# hx_esp32c5_cam.net
KiCad netlist of a schematic drawn in EasyEDA Pro
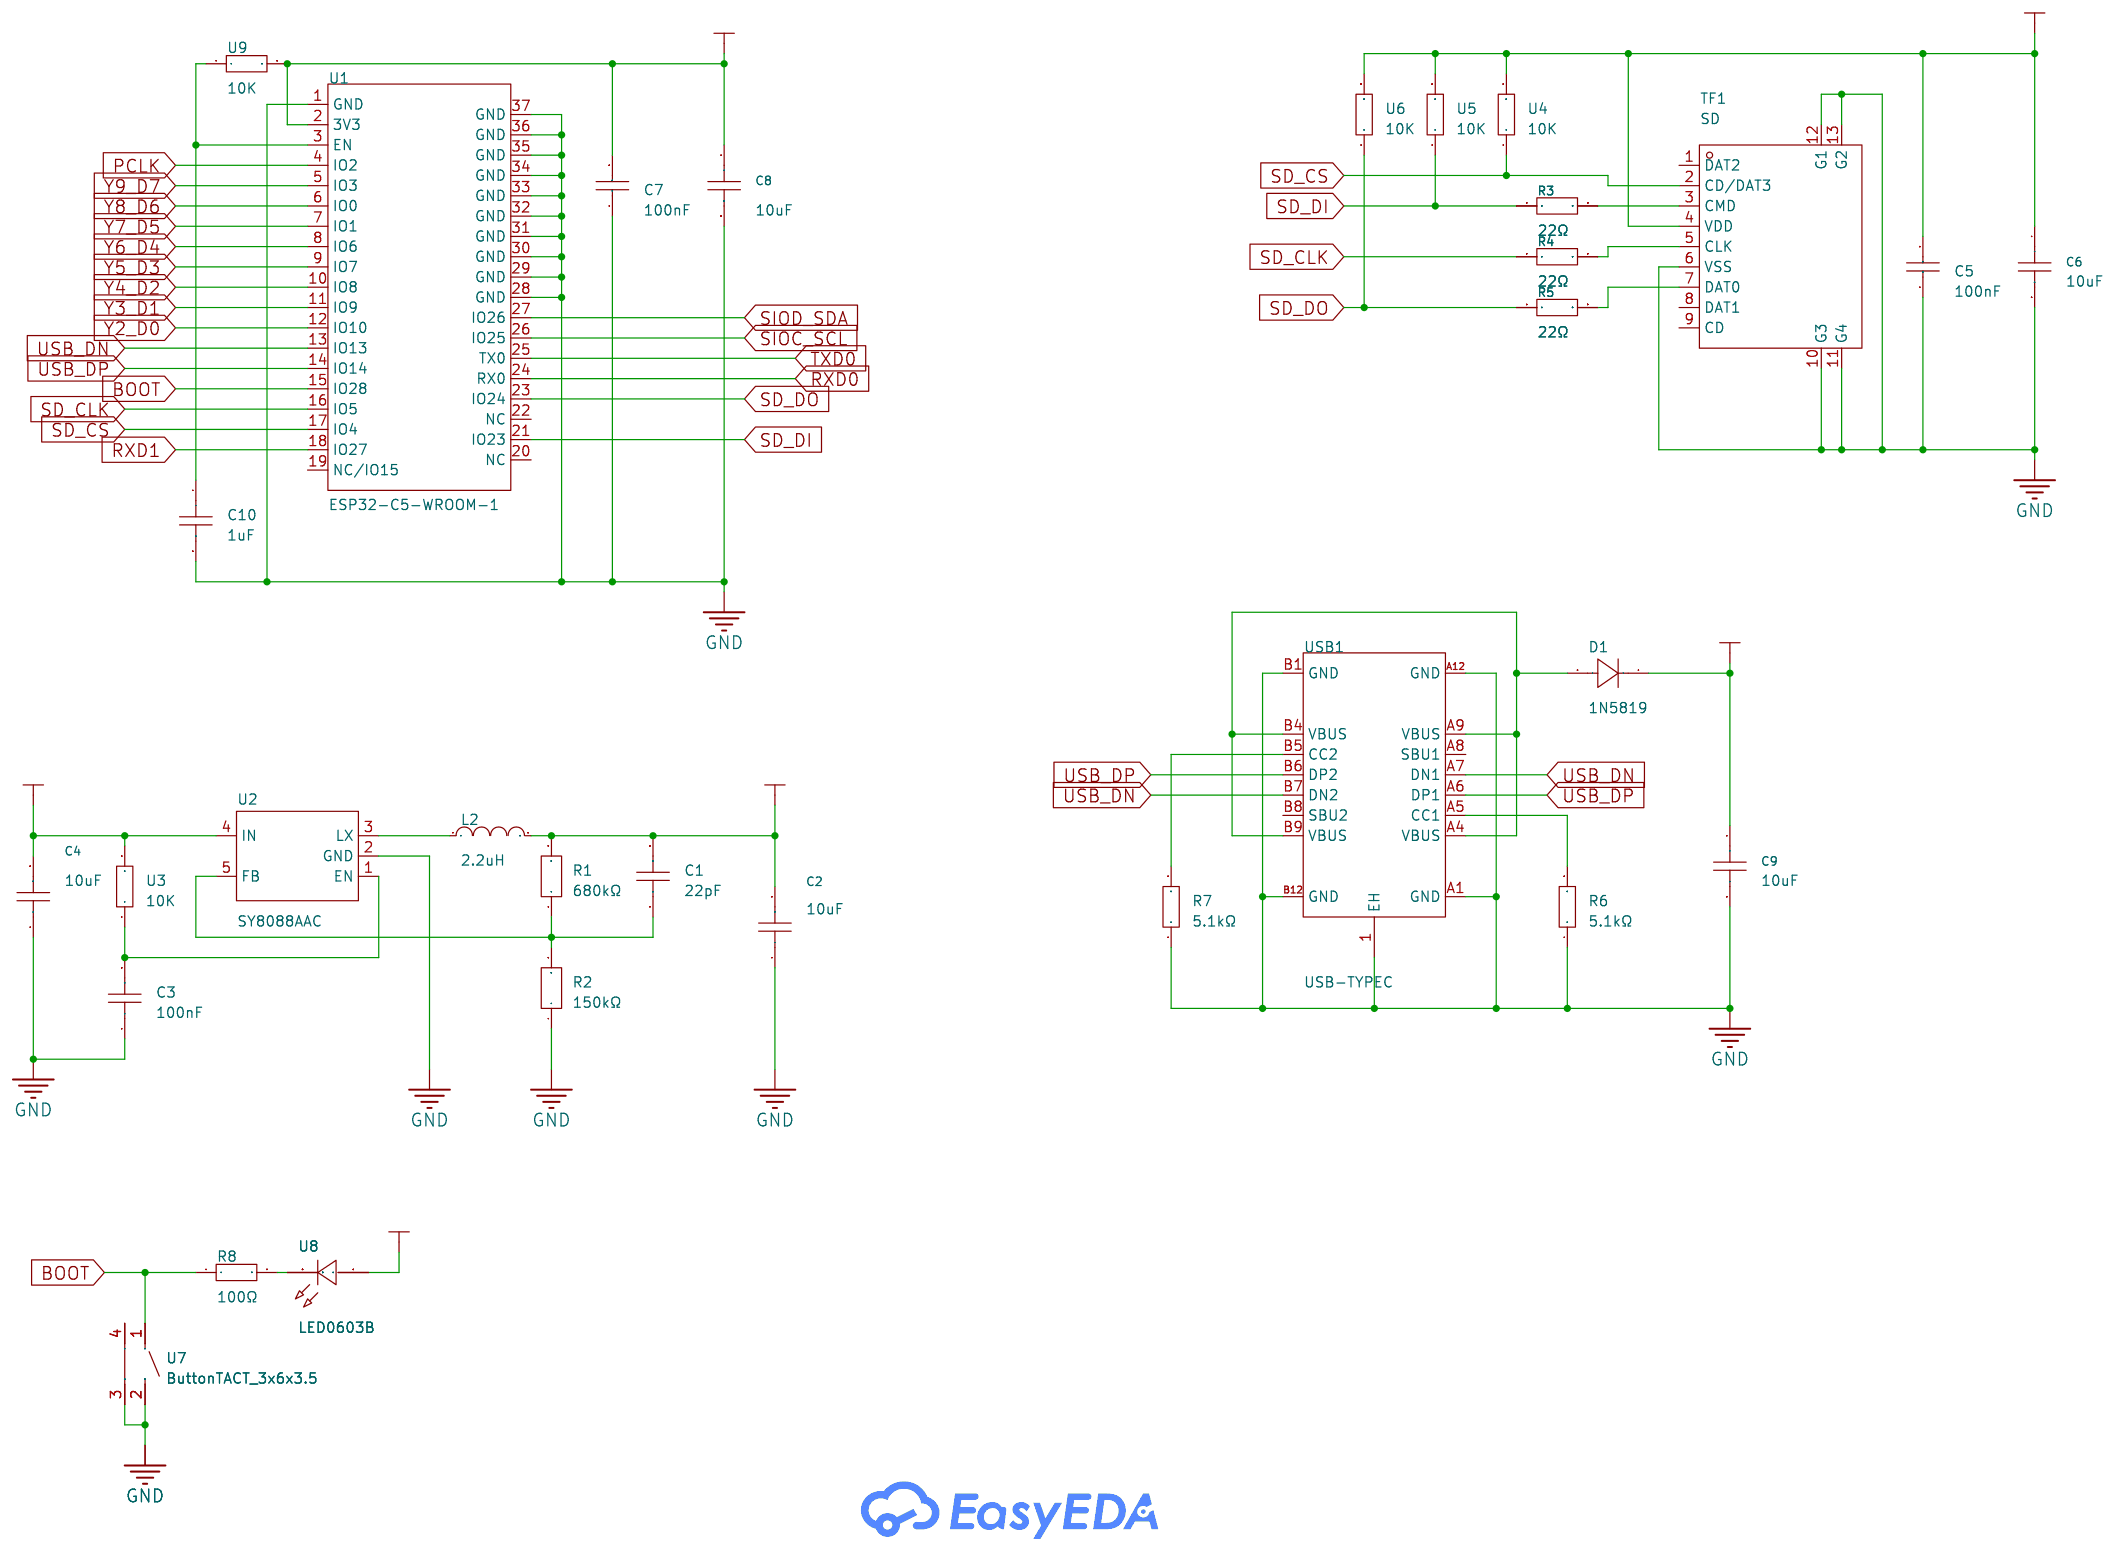
[diagram p0: schematic sheet]

(export (version "E")
  (design (tool "Eeschema 10.0.6"))
  (components
    (comp (ref "C1")
      (value "22pF")
      (footprint "easyedapro:C0603")
      (description "Capacitance:22pF Tolerance:±1% Tolerance:±1% Voltage Rating:50V Temperature Coefficient:NP0")
      (fields
        (field (name "Manufacturer Part") "CC0603FPNPO9BN220")
        (field (name "Manufacturer") "YAGEO(国巨)")
      )
      (libsource (lib "easyedapro") (part "CC0603FPNPO9BN220"))
    )
    (comp (ref "C2")
      (value "10uF")
      (footprint "easyedapro:C0603")
      (fields (field (name "Manufacturer") "SAMSUNG(三星)"))
      (libsource (lib "easyedapro") (part "10UF"))
    )
    (comp (ref "C3")
      (value "100nF")
      (footprint "easyedapro:C0805")
      (description "Capacitance:100nF Tolerance:±10% Tolerance:±10% Voltage Rating:50V Temperature Coefficient:X7R")
      (fields
        (field (name "Manufacturer Part") "CC0805KRX7R9BB104")
        (field (name "Manufacturer") "YAGEO(国巨)")
      )
      (libsource (lib "easyedapro") (part "CC0805KRX7R9BB104"))
    )
    (comp (ref "C4")
      (value "10uF")
      (footprint "easyedapro:C0603")
      (fields (field (name "Manufacturer") "SAMSUNG(三星)"))
      (libsource (lib "easyedapro") (part "10UF"))
    )
    (comp (ref "C5")
      (value "100nF")
      (footprint "easyedapro:C0805")
      (description "Capacitance:100nF Tolerance:±10% Tolerance:±10% Voltage Rating:100V Temperature Coefficient:X7R")
      (fields
        (field (name "Manufacturer Part") "CL21B104KCFNNNE")
        (field (name "Manufacturer") "SAMSUNG(三星)")
      )
      (libsource (lib "easyedapro") (part "CL21B104KCFNNNE"))
    )
    (comp (ref "C6")
      (value "10uF")
      (footprint "easyedapro:C0603")
      (fields (field (name "Manufacturer") "SAMSUNG(三星)"))
      (libsource (lib "easyedapro") (part "10UF"))
    )
    (comp (ref "C7")
      (value "100nF")
      (footprint "easyedapro:C0805")
      (description "Capacitance:100nF Tolerance:±10% Tolerance:±10% Voltage Rating:100V Temperature Coefficient:X7R")
      (fields
        (field (name "Manufacturer Part") "CL21B104KCFNNNE")
        (field (name "Manufacturer") "SAMSUNG(三星)")
      )
      (libsource (lib "easyedapro") (part "CL21B104KCFNNNE"))
    )
    (comp (ref "C8")
      (value "10uF")
      (footprint "easyedapro:C0603")
      (fields (field (name "Manufacturer") "SAMSUNG(三星)"))
      (libsource (lib "easyedapro") (part "10UF"))
    )
    (comp (ref "C9")
      (value "10uF")
      (footprint "easyedapro:C0603")
      (fields (field (name "Manufacturer") "SAMSUNG(三星)"))
      (libsource (lib "easyedapro") (part "10UF"))
    )
    (comp (ref "C10")
      (value "1uF")
      (footprint "easyedapro:C0603")
      (fields (field (name "Manufacturer Part") "CGB3B1X6S1C105K055AC") (field (name "Manufacturer") "TDK"))
      (libsource (lib "easyedapro") (part "CGB3B1X6S1C105K055AC"))
    )
    (comp (ref "D1")
      (value "1N5819")
      (footprint "easyedapro:SMA_L4.3-W2.7-LS5.1-RD")
      (libsource (lib "easyedapro") (part "1N5819_C2892330"))
    )
    (comp (ref "L2")
      (value "2.2uH")
      (footprint "easyedapro:IND-SMD_L2.0-W1.6_MHP201610")
      (description "Inductance:2.2uH Tolerance:±20% Tolerance:±20% Current Rating:1.6A DC Resistance(DCR):120mΩ")
      (fields
        (field (name "Manufacturer Part") "HPI201612P-2R2M")
        (field (name "Manufacturer") "3L COILS(三礼)")
      )
      (libsource (lib "easyedapro") (part "HPI201612P-2R2M"))
    )
    (comp (ref "R1")
      (value "680kΩ")
      (footprint "easyedapro:R0805")
      (fields
        (field (name "Manufacturer Part") "TC0525B6803T5E")
        (field (name "Manufacturer") "UNI-ROYAL(厚声)")
      )
      (libsource (lib "easyedapro") (part "TC0525B6803T5E"))
    )
    (comp (ref "R2")
      (value "150kΩ")
      (footprint "easyedapro:R0805")
      (fields
        (field (name "Manufacturer Part") "AS05W2J0154T5E")
        (field (name "Manufacturer") "UNI-ROYAL(厚声)")
      )
      (libsource (lib "easyedapro") (part "AS05W2J0154T5E"))
    )
    (comp (ref "R3")
      (value "22Ω")
      (footprint "easyedapro:R0805")
      (fields (field (name "Manufacturer Part") "RMC0805225%N") (field (name "Manufacturer") "Tyohm(幸亚电阻)"))
      (libsource (lib "easyedapro") (part "RMC0805225%N"))
    )
    (comp (ref "R4")
      (value "22Ω")
      (footprint "easyedapro:R0805")
      (fields (field (name "Manufacturer Part") "RMC0805225%N") (field (name "Manufacturer") "Tyohm(幸亚电阻)"))
      (libsource (lib "easyedapro") (part "RMC0805225%N"))
    )
    (comp (ref "R5")
      (value "22Ω")
      (footprint "easyedapro:R0805")
      (fields (field (name "Manufacturer Part") "RMC0805225%N") (field (name "Manufacturer") "Tyohm(幸亚电阻)"))
      (libsource (lib "easyedapro") (part "RMC0805225%N"))
    )
    (comp (ref "R6")
      (value "5.1kΩ")
      (footprint "easyedapro:R0805")
      (fields (field (name "Manufacturer Part") "AECR0805F5K10K9") (field (name "Manufacturer") "RESI(开步睿思)"))
      (libsource (lib "easyedapro") (part "AECR0805F5K10K9"))
    )
    (comp (ref "R7")
      (value "5.1kΩ")
      (footprint "easyedapro:R0805")
      (fields (field (name "Manufacturer Part") "AECR0805F5K10K9") (field (name "Manufacturer") "RESI(开步睿思)"))
      (libsource (lib "easyedapro") (part "AECR0805F5K10K9"))
    )
    (comp (ref "R8")
      (value "100Ω")
      (footprint "easyedapro:R0805")
      (fields (field (name "Manufacturer Part") "MCR10EZHJ101") (field (name "Manufacturer") "ROHM(罗姆)"))
      (libsource (lib "easyedapro") (part "MCR10EZHJ101"))
    )
    (comp (ref "TF1")
      (value "SD")
      (footprint "easyedapro:TF-SMD_TF-15-15")
      (libsource (lib "easyedapro") (part "SD"))
    )
    (comp (ref "U1")
      (value "ESP32-C5-WROOM-1")
      (footprint "easyedapro:COMM-SMD_37P-P1.27-L27.5-W18.0-ESP32-C5-WROOM-1")
      (libsource (lib "easyedapro") (part "ESP32-C5-WROOM-1"))
    )
    (comp (ref "U2")
      (value "SY8088AAC")
      (footprint "easyedapro:SOT-23-5_L3.0-W1.7-P0.95-LS2.8-BR")
      (fields (field (name "Manufacturer") "silergy(矽力杰)"))
      (libsource (lib "easyedapro") (part "SY8088AAC"))
    )
    (comp (ref "U3") (value "10K") (footprint "easyedapro:R0805") (libsource (lib "easyedapro") (part "10K")))
    (comp (ref "U4") (value "10K") (footprint "easyedapro:R0805") (libsource (lib "easyedapro") (part "10K")))
    (comp (ref "U5") (value "10K") (footprint "easyedapro:R0805") (libsource (lib "easyedapro") (part "10K")))
    (comp (ref "U6") (value "10K") (footprint "easyedapro:R0805") (libsource (lib "easyedapro") (part "10K")))
    (comp (ref "U7")
      (value "ButtonTACT_3x6x3.5")
      (footprint "easyedapro:SW-SMD_L7.8-W3.5-P4.00-EH")
      (libsource (lib "easyedapro") (part "BUTTONTACT_3X6X3.5"))
    )
    (comp (ref "U8")
      (value "LED0603B")
      (footprint "easyedapro:LED0603-R-RD_BLUE")
      (libsource (lib "easyedapro") (part "LED0603B_C9900038277"))
    )
    (comp (ref "U9") (value "10K") (footprint "easyedapro:R0805") (libsource (lib "easyedapro") (part "10K")))
    (comp (ref "USB1")
      (value "USB-TYPEC")
      (footprint "easyedapro:TYPE-C-SMD_16P-EH4")
      (libsource (lib "easyedapro") (part "USB-TYPEC"))
    )
  )
  (nets
    (net (code "1") (name "BOOT") (class "Default")
      (node (ref "R8") (pin "1") (pinfunction "1_1") (pintype "unspecified"))
      (node (ref "U1") (pin "15") (pinfunction "IO28_15") (pintype "unspecified"))
      (node (ref "U7") (pin "1") (pinfunction "1_1") (pintype "unspecified"))
    )
    (net (code "2") (name "GND") (class "Default")
      (node (ref "C10") (pin "2") (pinfunction "2_2") (pintype "unspecified"))
      (node (ref "C2") (pin "1") (pinfunction "1_1") (pintype "input"))
      (node (ref "C3") (pin "1") (pinfunction "1_1") (pintype "unspecified"))
      (node (ref "C4") (pin "1") (pinfunction "1_1") (pintype "input"))
      (node (ref "C5") (pin "1") (pinfunction "1_1") (pintype "input"))
      (node (ref "C6") (pin "2") (pinfunction "2_2") (pintype "input"))
      (node (ref "C7") (pin "1") (pinfunction "1_1") (pintype "input"))
      (node (ref "C8") (pin "2") (pinfunction "2_2") (pintype "input"))
      (node (ref "C9") (pin "2") (pinfunction "2_2") (pintype "input"))
      (node (ref "R2") (pin "1") (pinfunction "1_1") (pintype "unspecified"))
      (node (ref "R6") (pin "1") (pinfunction "1_1") (pintype "unspecified"))
      (node (ref "R7") (pin "1") (pinfunction "1_1") (pintype "unspecified"))
      (node (ref "TF1") (pin "10") (pinfunction "G3_10") (pintype "unspecified"))
      (node (ref "TF1") (pin "11") (pinfunction "G4_11") (pintype "unspecified"))
      (node (ref "TF1") (pin "12") (pinfunction "G1_12") (pintype "unspecified"))
      (node (ref "TF1") (pin "13") (pinfunction "G2_13") (pintype "unspecified"))
      (node (ref "TF1") (pin "6") (pinfunction "VSS_6") (pintype "unspecified"))
      (node (ref "U1") (pin "1") (pinfunction "GND_1") (pintype "unspecified"))
      (node (ref "U1") (pin "28") (pinfunction "GND_28") (pintype "unspecified"))
      (node (ref "U1") (pin "29") (pinfunction "GND_29") (pintype "unspecified"))
      (node (ref "U1") (pin "30") (pinfunction "GND_30") (pintype "unspecified"))
      (node (ref "U1") (pin "31") (pinfunction "GND_31") (pintype "unspecified"))
      (node (ref "U1") (pin "32") (pinfunction "GND_32") (pintype "unspecified"))
      (node (ref "U1") (pin "33") (pinfunction "GND_33") (pintype "unspecified"))
      (node (ref "U1") (pin "34") (pinfunction "GND_34") (pintype "unspecified"))
      (node (ref "U1") (pin "35") (pinfunction "GND_35") (pintype "unspecified"))
      (node (ref "U1") (pin "36") (pinfunction "GND_36") (pintype "unspecified"))
      (node (ref "U1") (pin "37") (pinfunction "GND_37") (pintype "unspecified"))
      (node (ref "U2") (pin "2") (pinfunction "GND_2") (pintype "unspecified"))
      (node (ref "U7") (pin "2") (pinfunction "2_2") (pintype "unspecified"))
      (node (ref "U7") (pin "3") (pinfunction "3_3") (pintype "unspecified"))
      (node (ref "USB1") (pin "1") (pinfunction "EH_1") (pintype "unspecified"))
      (node (ref "USB1") (pin "A1") (pinfunction "GND_A1") (pintype "unspecified"))
      (node (ref "USB1") (pin "A12") (pinfunction "GND_A12") (pintype "unspecified"))
      (node (ref "USB1") (pin "B1") (pinfunction "GND_B1") (pintype "unspecified"))
      (node (ref "USB1") (pin "B12") (pinfunction "GND_B12") (pintype "unspecified"))
    )
    (net (code "3") (name "Net-(D1-A)") (class "Default")
      (node (ref "D1") (pin "2") (pinfunction "A_2") (pintype "input"))
      (node (ref "USB1") (pin "A4") (pinfunction "VBUS_A4") (pintype "unspecified"))
      (node (ref "USB1") (pin "A9") (pinfunction "VBUS_A9") (pintype "unspecified"))
      (node (ref "USB1") (pin "B4") (pinfunction "VBUS_B4") (pintype "unspecified"))
      (node (ref "USB1") (pin "B9") (pinfunction "VBUS_B9") (pintype "unspecified"))
    )
    (net (code "4") (name "Net-(TF1-CLK)") (class "Default")
      (node (ref "R4") (pin "2") (pinfunction "2_2") (pintype "input"))
      (node (ref "TF1") (pin "5") (pinfunction "CLK_5") (pintype "unspecified"))
    )
    (net (code "5") (name "Net-(TF1-CMD)") (class "Default")
      (node (ref "R3") (pin "2") (pinfunction "2_2") (pintype "input"))
      (node (ref "TF1") (pin "3") (pinfunction "CMD_3") (pintype "unspecified"))
    )
    (net (code "6") (name "Net-(TF1-DAT0)") (class "Default")
      (node (ref "R5") (pin "2") (pinfunction "2_2") (pintype "input"))
      (node (ref "TF1") (pin "7") (pinfunction "DAT0_7") (pintype "unspecified"))
    )
    (net (code "7") (name "Net-(U1-EN)") (class "Default")
      (node (ref "C10") (pin "1") (pinfunction "1_1") (pintype "unspecified"))
      (node (ref "U1") (pin "3") (pinfunction "EN_3") (pintype "unspecified"))
      (node (ref "U9") (pin "1") (pinfunction "1_1") (pintype "unspecified"))
    )
    (net (code "8") (name "Net-(U2-EN)") (class "Default")
      (node (ref "C3") (pin "2") (pinfunction "2_2") (pintype "unspecified"))
      (node (ref "U2") (pin "1") (pinfunction "EN_1") (pintype "unspecified"))
      (node (ref "U3") (pin "1") (pinfunction "1_1") (pintype "unspecified"))
    )
    (net (code "9") (name "Net-(U2-FB)") (class "Default")
      (node (ref "C1") (pin "1") (pinfunction "1_1") (pintype "unspecified"))
      (node (ref "R1") (pin "1") (pinfunction "1_1") (pintype "unspecified"))
      (node (ref "R2") (pin "2") (pinfunction "2_2") (pintype "unspecified"))
      (node (ref "U2") (pin "5") (pinfunction "FB_5") (pintype "unspecified"))
    )
    (net (code "10") (name "Net-(U2-LX)") (class "Default")
      (node (ref "L2") (pin "1") (pinfunction "1_1") (pintype "input"))
      (node (ref "U2") (pin "3") (pinfunction "LX_3") (pintype "unspecified"))
    )
    (net (code "11") (name "Net-(U8-C)") (class "Default")
      (node (ref "R8") (pin "2") (pinfunction "2_2") (pintype "unspecified"))
      (node (ref "U8") (pin "2") (pinfunction "C_2") (pintype "unspecified"))
    )
    (net (code "12") (name "Net-(USB1-CC1)") (class "Default")
      (node (ref "R6") (pin "2") (pinfunction "2_2") (pintype "unspecified"))
      (node (ref "USB1") (pin "A5") (pinfunction "CC1_A5") (pintype "unspecified"))
    )
    (net (code "13") (name "Net-(USB1-CC2)") (class "Default")
      (node (ref "R7") (pin "2") (pinfunction "2_2") (pintype "unspecified"))
      (node (ref "USB1") (pin "B5") (pinfunction "CC2_B5") (pintype "unspecified"))
    )
    (net (code "14") (name "PCLK") (class "Default")
      (node (ref "U1") (pin "4") (pinfunction "IO2_4") (pintype "unspecified"))
    )
    (net (code "15") (name "RXD0") (class "Default")
      (node (ref "U1") (pin "24") (pinfunction "RX0_24") (pintype "unspecified"))
    )
    (net (code "16") (name "RXD1") (class "Default")
      (node (ref "U1") (pin "18") (pinfunction "IO27_18") (pintype "unspecified"))
    )
    (net (code "17") (name "SD_CLK") (class "Default")
      (node (ref "R4") (pin "1") (pinfunction "1_1") (pintype "input"))
      (node (ref "U1") (pin "16") (pinfunction "IO5_16") (pintype "unspecified"))
    )
    (net (code "18") (name "SD_CS") (class "Default")
      (node (ref "TF1") (pin "2") (pinfunction "CD/DAT3_2") (pintype "unspecified"))
      (node (ref "U1") (pin "17") (pinfunction "IO4_17") (pintype "unspecified"))
      (node (ref "U4") (pin "1") (pinfunction "1_1") (pintype "unspecified"))
    )
    (net (code "19") (name "SD_DI") (class "Default")
      (node (ref "R3") (pin "1") (pinfunction "1_1") (pintype "input"))
      (node (ref "U1") (pin "21") (pinfunction "IO23_21") (pintype "unspecified"))
      (node (ref "U5") (pin "1") (pinfunction "1_1") (pintype "unspecified"))
    )
    (net (code "20") (name "SD_DO") (class "Default")
      (node (ref "R5") (pin "1") (pinfunction "1_1") (pintype "input"))
      (node (ref "U1") (pin "23") (pinfunction "IO24_23") (pintype "unspecified"))
      (node (ref "U6") (pin "1") (pinfunction "1_1") (pintype "unspecified"))
    )
    (net (code "21") (name "SIOC_SCL") (class "Default")
      (node (ref "U1") (pin "26") (pinfunction "IO25_26") (pintype "unspecified"))
    )
    (net (code "22") (name "SIOD_SDA") (class "Default")
      (node (ref "U1") (pin "27") (pinfunction "IO26_27") (pintype "unspecified"))
    )
    (net (code "23") (name "TXD0") (class "Default")
      (node (ref "U1") (pin "25") (pinfunction "TX0_25") (pintype "unspecified"))
    )
    (net (code "24") (name "USB_DN") (class "Default")
      (node (ref "U1") (pin "13") (pinfunction "IO13_13") (pintype "unspecified"))
      (node (ref "USB1") (pin "A7") (pinfunction "DN1_A7") (pintype "unspecified"))
      (node (ref "USB1") (pin "B7") (pinfunction "DN2_B7") (pintype "unspecified"))
    )
    (net (code "25") (name "USB_DP") (class "Default")
      (node (ref "U1") (pin "14") (pinfunction "IO14_14") (pintype "unspecified"))
      (node (ref "USB1") (pin "A6") (pinfunction "DP1_A6") (pintype "unspecified"))
      (node (ref "USB1") (pin "B6") (pinfunction "DP2_B6") (pintype "unspecified"))
    )
    (net (code "26") (name "VCC_3.3V") (class "Default")
      (node (ref "C1") (pin "2") (pinfunction "2_2") (pintype "unspecified"))
      (node (ref "C2") (pin "2") (pinfunction "2_2") (pintype "input"))
      (node (ref "C5") (pin "2") (pinfunction "2_2") (pintype "input"))
      (node (ref "C6") (pin "1") (pinfunction "1_1") (pintype "input"))
      (node (ref "C7") (pin "2") (pinfunction "2_2") (pintype "input"))
      (node (ref "C8") (pin "1") (pinfunction "1_1") (pintype "input"))
      (node (ref "L2") (pin "2") (pinfunction "2_2") (pintype "input"))
      (node (ref "R1") (pin "2") (pinfunction "2_2") (pintype "unspecified"))
      (node (ref "TF1") (pin "4") (pinfunction "VDD_4") (pintype "unspecified"))
      (node (ref "U1") (pin "2") (pinfunction "3V3_2") (pintype "unspecified"))
      (node (ref "U4") (pin "2") (pinfunction "2_2") (pintype "unspecified"))
      (node (ref "U5") (pin "2") (pinfunction "2_2") (pintype "unspecified"))
      (node (ref "U6") (pin "2") (pinfunction "2_2") (pintype "unspecified"))
      (node (ref "U8") (pin "1") (pinfunction "A_1") (pintype "unspecified"))
      (node (ref "U9") (pin "2") (pinfunction "2_2") (pintype "unspecified"))
    )
    (net (code "27") (name "VCC_5V") (class "Default")
      (node (ref "C4") (pin "2") (pinfunction "2_2") (pintype "input"))
      (node (ref "C9") (pin "1") (pinfunction "1_1") (pintype "input"))
      (node (ref "D1") (pin "1") (pinfunction "K_1") (pintype "input"))
      (node (ref "U2") (pin "4") (pinfunction "IN_4") (pintype "unspecified"))
      (node (ref "U3") (pin "2") (pinfunction "2_2") (pintype "unspecified"))
    )
    (net (code "28") (name "Y2_D0") (class "Default")
      (node (ref "U1") (pin "12") (pinfunction "IO10_12") (pintype "unspecified"))
    )
    (net (code "29") (name "Y3_D1") (class "Default")
      (node (ref "U1") (pin "11") (pinfunction "IO9_11") (pintype "unspecified"))
    )
    (net (code "30") (name "Y4_D2") (class "Default")
      (node (ref "U1") (pin "10") (pinfunction "IO8_10") (pintype "unspecified"))
    )
    (net (code "31") (name "Y5_D3") (class "Default")
      (node (ref "U1") (pin "9") (pinfunction "IO7_9") (pintype "unspecified"))
    )
    (net (code "32") (name "Y6_D4") (class "Default")
      (node (ref "U1") (pin "8") (pinfunction "IO6_8") (pintype "unspecified"))
    )
    (net (code "33") (name "Y7_D5") (class "Default")
      (node (ref "U1") (pin "7") (pinfunction "IO1_7") (pintype "unspecified"))
    )
    (net (code "34") (name "Y8_D6") (class "Default")
      (node (ref "U1") (pin "6") (pinfunction "IO0_6") (pintype "unspecified"))
    )
    (net (code "35") (name "Y9_D7") (class "Default")
      (node (ref "U1") (pin "5") (pinfunction "IO3_5") (pintype "unspecified"))
    )
    (net (code "36") (name "unconnected-(TF1-CD-Pad9)") (class "Default")
      (node (ref "TF1") (pin "9") (pinfunction "CD_9") (pintype "unspecified"))
    )
    (net (code "37") (name "unconnected-(TF1-DAT1-Pad8)") (class "Default")
      (node (ref "TF1") (pin "8") (pinfunction "DAT1_8") (pintype "unspecified"))
    )
    (net (code "38") (name "unconnected-(TF1-DAT2-Pad1)") (class "Default")
      (node (ref "TF1") (pin "1") (pinfunction "DAT2_1") (pintype "unspecified"))
    )
    (net (code "39") (name "unconnected-(U1-NC-Pad20)") (class "Default")
      (node (ref "U1") (pin "20") (pinfunction "NC_20") (pintype "unspecified"))
    )
    (net (code "40") (name "unconnected-(U1-NC-Pad22)") (class "Default")
      (node (ref "U1") (pin "22") (pinfunction "NC_22") (pintype "unspecified"))
    )
    (net (code "41") (name "unconnected-(U1-NC{slash}IO15-Pad19)") (class "Default")
      (node (ref "U1") (pin "19") (pinfunction "NC/IO15_19") (pintype "unspecified"))
    )
    (net (code "42") (name "unconnected-(U7-Pad4)") (class "Default")
      (node (ref "U7") (pin "4") (pinfunction "4_4") (pintype "unspecified"))
    )
    (net (code "43") (name "unconnected-(USB1-SBU1-PadA8)") (class "Default")
      (node (ref "USB1") (pin "A8") (pinfunction "SBU1_A8") (pintype "unspecified"))
    )
    (net (code "44") (name "unconnected-(USB1-SBU2-PadB8)") (class "Default")
      (node (ref "USB1") (pin "B8") (pinfunction "SBU2_B8") (pintype "unspecified"))
    )
  )
)
